# 05_ServoStage_v1.net
KiCad netlist of a schematic drawn in EAGLE
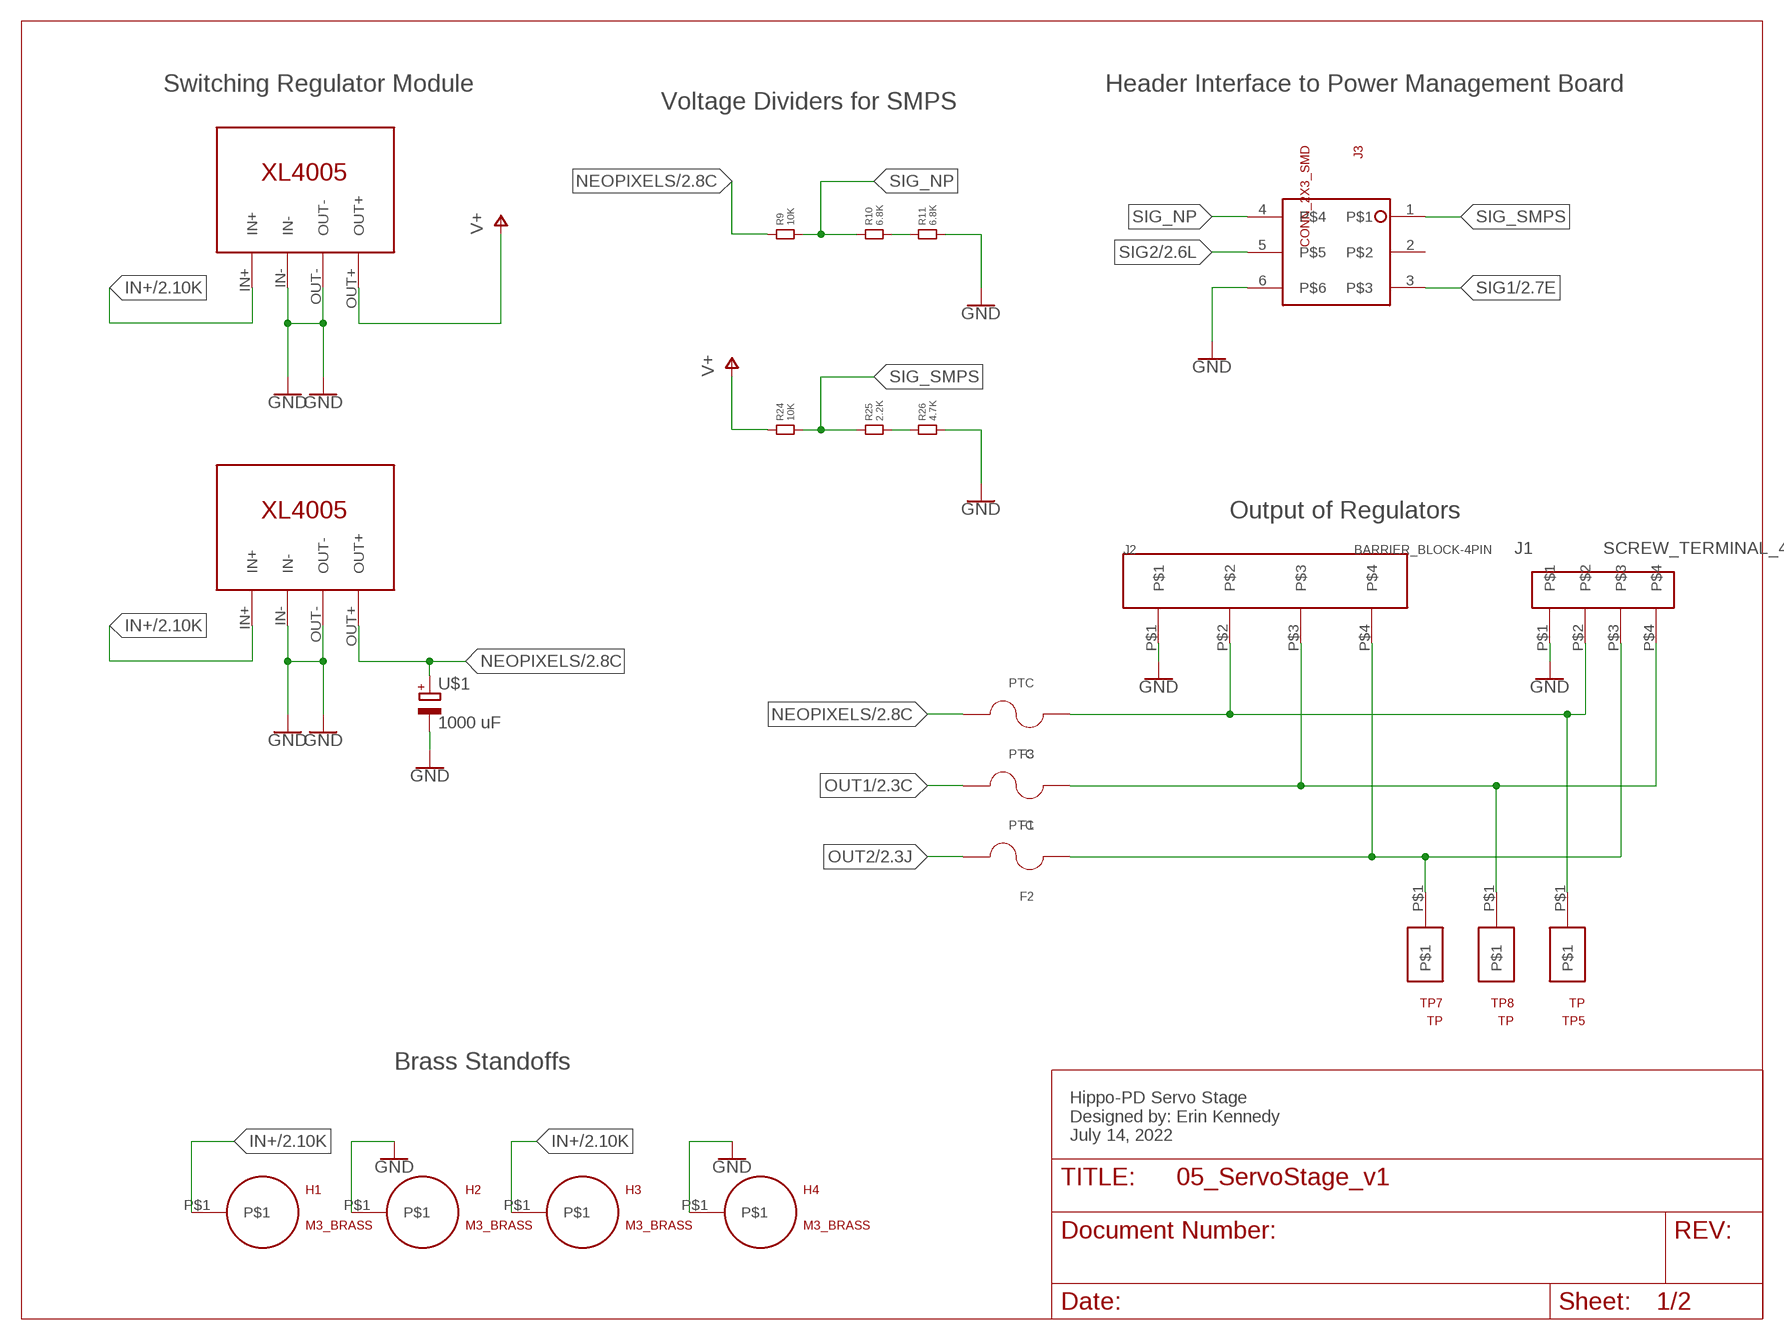
[diagram p0: schematic, sheet 1]
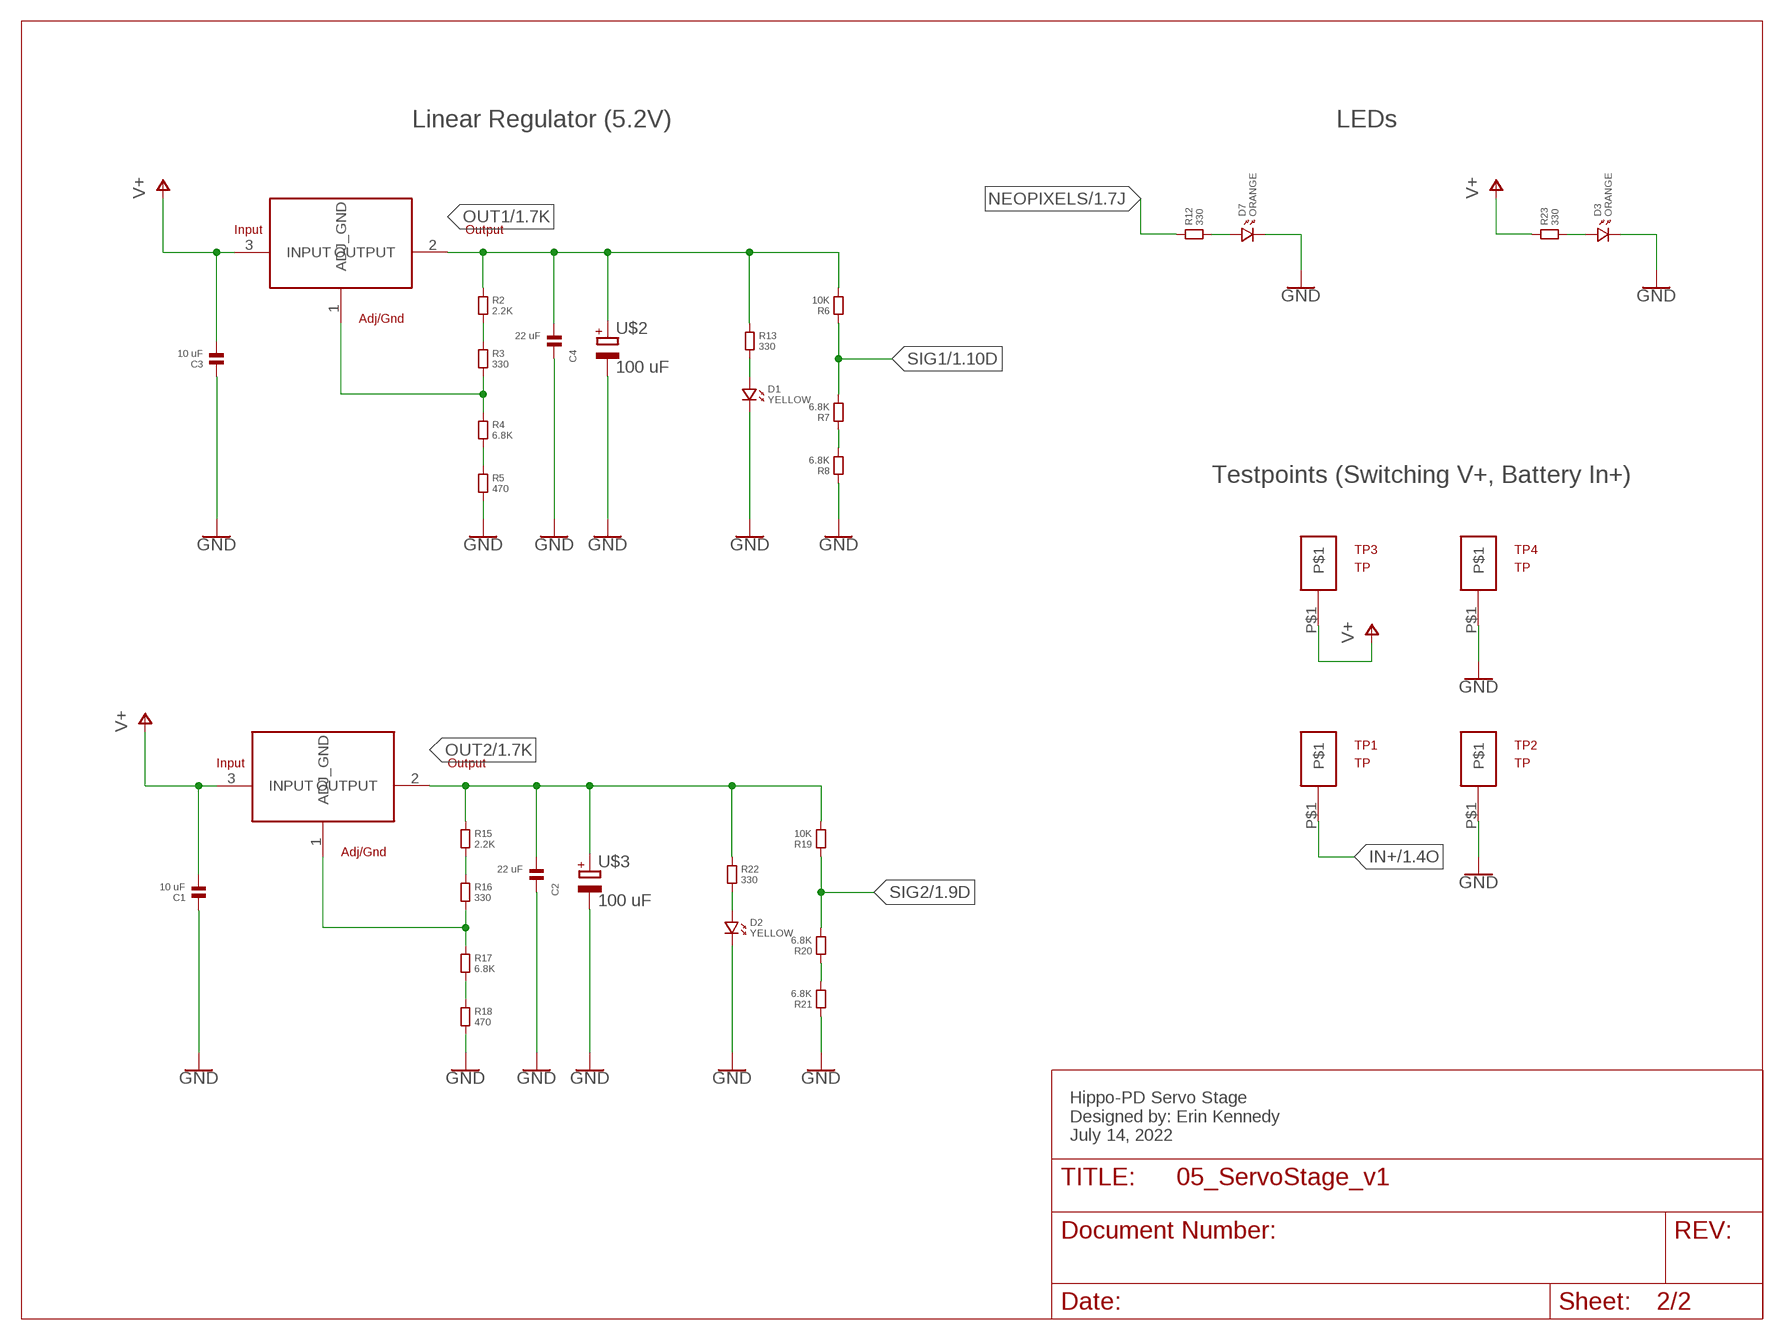
[diagram p1: schematic, sheet 2]

(export (version "E")
  (design (tool "Eeschema 10.0.6"))
  (components
    (comp (ref "C1")
      (value "10 uF")
      (footprint "eagle-import:1206")
      (libsource (lib "eagle-import") (part "CAPACITOR.1206"))
    )
    (comp (ref "C2")
      (value "22 uF")
      (footprint "eagle-import:1206")
      (libsource (lib "eagle-import") (part "CAPACITOR.1206"))
    )
    (comp (ref "C3")
      (value "10 uF")
      (footprint "eagle-import:1206")
      (libsource (lib "eagle-import") (part "CAPACITOR.1206"))
    )
    (comp (ref "C4")
      (value "22 uF")
      (footprint "eagle-import:1206")
      (libsource (lib "eagle-import") (part "CAPACITOR.1206"))
    )
    (comp (ref "D1")
      (value "YELLOW")
      (footprint "eagle-import:1206.LED")
      (libsource (lib "eagle-import") (part "LED.1206"))
    )
    (comp (ref "D2")
      (value "YELLOW")
      (footprint "eagle-import:1206.LED")
      (libsource (lib "eagle-import") (part "LED.1206"))
    )
    (comp (ref "D3")
      (value "ORANGE")
      (footprint "eagle-import:1206.LED")
      (libsource (lib "eagle-import") (part "LED.1206"))
    )
    (comp (ref "D7")
      (value "ORANGE")
      (footprint "eagle-import:1206.LED")
      (libsource (lib "eagle-import") (part "LED.1206"))
    )
    (comp (ref "R1")
      (value "AZ1084C")
      (footprint "eagle-import:AZ1084C")
      (libsource (lib "eagle-import") (part "AZ1084C"))
    )
    (comp (ref "R2")
      (value "2.2K")
      (footprint "eagle-import:1206")
      (libsource (lib "eagle-import") (part "RESISTOR.1206"))
    )
    (comp (ref "R3")
      (value "330")
      (footprint "eagle-import:1206")
      (libsource (lib "eagle-import") (part "RESISTOR.1206"))
    )
    (comp (ref "R4")
      (value "6.8K")
      (footprint "eagle-import:1206")
      (libsource (lib "eagle-import") (part "RESISTOR.1206"))
    )
    (comp (ref "R5")
      (value "470")
      (footprint "eagle-import:1206")
      (libsource (lib "eagle-import") (part "RESISTOR.1206"))
    )
    (comp (ref "R6")
      (value "10K")
      (footprint "eagle-import:1206")
      (libsource (lib "eagle-import") (part "RESISTOR.1206"))
    )
    (comp (ref "R7")
      (value "6.8K")
      (footprint "eagle-import:1206")
      (libsource (lib "eagle-import") (part "RESISTOR.1206"))
    )
    (comp (ref "R8")
      (value "6.8K")
      (footprint "eagle-import:1206")
      (libsource (lib "eagle-import") (part "RESISTOR.1206"))
    )
    (comp (ref "R12")
      (value "330")
      (footprint "eagle-import:1206")
      (libsource (lib "eagle-import") (part "RESISTOR.1206"))
    )
    (comp (ref "R13")
      (value "330")
      (footprint "eagle-import:1206")
      (libsource (lib "eagle-import") (part "RESISTOR.1206"))
    )
    (comp (ref "R14")
      (value "AZ1084C")
      (footprint "eagle-import:AZ1084C")
      (libsource (lib "eagle-import") (part "AZ1084C"))
    )
    (comp (ref "R15")
      (value "2.2K")
      (footprint "eagle-import:1206")
      (libsource (lib "eagle-import") (part "RESISTOR.1206"))
    )
    (comp (ref "R16")
      (value "330")
      (footprint "eagle-import:1206")
      (libsource (lib "eagle-import") (part "RESISTOR.1206"))
    )
    (comp (ref "R17")
      (value "6.8K")
      (footprint "eagle-import:1206")
      (libsource (lib "eagle-import") (part "RESISTOR.1206"))
    )
    (comp (ref "R18")
      (value "470")
      (footprint "eagle-import:1206")
      (libsource (lib "eagle-import") (part "RESISTOR.1206"))
    )
    (comp (ref "R19")
      (value "10K")
      (footprint "eagle-import:1206")
      (libsource (lib "eagle-import") (part "RESISTOR.1206"))
    )
    (comp (ref "R20")
      (value "6.8K")
      (footprint "eagle-import:1206")
      (libsource (lib "eagle-import") (part "RESISTOR.1206"))
    )
    (comp (ref "R21")
      (value "6.8K")
      (footprint "eagle-import:1206")
      (libsource (lib "eagle-import") (part "RESISTOR.1206"))
    )
    (comp (ref "R22")
      (value "330")
      (footprint "eagle-import:1206")
      (libsource (lib "eagle-import") (part "RESISTOR.1206"))
    )
    (comp (ref "R23")
      (value "330")
      (footprint "eagle-import:1206")
      (libsource (lib "eagle-import") (part "RESISTOR.1206"))
    )
    (comp (ref "TP1") (value "TP") (footprint "eagle-import:TP") (libsource (lib "eagle-import") (part "TP")))
    (comp (ref "TP2") (value "TP") (footprint "eagle-import:TP") (libsource (lib "eagle-import") (part "TP")))
    (comp (ref "TP3") (value "TP") (footprint "eagle-import:TP") (libsource (lib "eagle-import") (part "TP")))
    (comp (ref "TP4") (value "TP") (footprint "eagle-import:TP") (libsource (lib "eagle-import") (part "TP")))
    (comp (ref "U$2")
      (value "100 uF")
      (footprint "eagle-import:ELECTROLYTIC_CAP")
      (fields (field (name "MF") "Wurth Electronics") (field (name "MP") "865080545012"))
      (libsource (lib "eagle-import") (part "ELECTROLYTIC_CAP"))
    )
    (comp (ref "U$3")
      (value "100 uF")
      (footprint "eagle-import:ELECTROLYTIC_CAP")
      (fields (field (name "MF") "Wurth Electronics") (field (name "MP") "865080545012"))
      (libsource (lib "eagle-import") (part "ELECTROLYTIC_CAP"))
    )
    (comp (ref "F1")
      (value "PTC")
      (footprint "eagle-import:PTC")
      (fields (field (name "MF") "Bel Fuse") (field (name "MP") "0ZCF0075AF2C"))
      (libsource (lib "eagle-import") (part "PTC"))
    )
    (comp (ref "F2")
      (value "PTC")
      (footprint "eagle-import:PTC")
      (fields (field (name "MF") "Bel Fuse") (field (name "MP") "0ZCF0075AF2C"))
      (libsource (lib "eagle-import") (part "PTC"))
    )
    (comp (ref "F3")
      (value "PTC")
      (footprint "eagle-import:PTC")
      (fields (field (name "MF") "Bel Fuse") (field (name "MP") "0ZCF0075AF2C"))
      (libsource (lib "eagle-import") (part "PTC"))
    )
    (comp (ref "H1")
      (value "M3_BRASS")
      (footprint "eagle-import:M3_BRASS")
      (libsource (lib "eagle-import") (part "M3_BRASS"))
    )
    (comp (ref "H2")
      (value "M3_BRASS")
      (footprint "eagle-import:M3_BRASS")
      (libsource (lib "eagle-import") (part "M3_BRASS"))
    )
    (comp (ref "H3")
      (value "M3_BRASS")
      (footprint "eagle-import:M3_BRASS")
      (libsource (lib "eagle-import") (part "M3_BRASS"))
    )
    (comp (ref "H4")
      (value "M3_BRASS")
      (footprint "eagle-import:M3_BRASS")
      (libsource (lib "eagle-import") (part "M3_BRASS"))
    )
    (comp (ref "J1")
      (value "SCREW_TERMINAL_4")
      (footprint "eagle-import:SCREW_TERM_4")
      (libsource (lib "eagle-import") (part "SCREW_TERMINAL_4"))
    )
    (comp (ref "J2")
      (value "BARRIER_BLOCK-4PIN")
      (footprint "eagle-import:BARRIERBLOCK-4PIN")
      (libsource (lib "eagle-import") (part "BARRIER_BLOCK-4PIN"))
    )
    (comp (ref "J3")
      (value "CONN_2X3_SMD")
      (footprint "eagle-import:2X3_SMD_CONNECTOR")
      (libsource (lib "eagle-import") (part "CONN_2X3_SMD"))
    )
    (comp (ref "R9")
      (value "10K")
      (footprint "eagle-import:1206")
      (libsource (lib "eagle-import") (part "RESISTOR.1206"))
    )
    (comp (ref "R10")
      (value "6.8K")
      (footprint "eagle-import:1206")
      (libsource (lib "eagle-import") (part "RESISTOR.1206"))
    )
    (comp (ref "R11")
      (value "6.8K")
      (footprint "eagle-import:1206")
      (libsource (lib "eagle-import") (part "RESISTOR.1206"))
    )
    (comp (ref "R24")
      (value "10K")
      (footprint "eagle-import:1206")
      (libsource (lib "eagle-import") (part "RESISTOR.1206"))
    )
    (comp (ref "R25")
      (value "2.2K")
      (footprint "eagle-import:1206")
      (libsource (lib "eagle-import") (part "RESISTOR.1206"))
    )
    (comp (ref "R26")
      (value "4.7K")
      (footprint "eagle-import:1206")
      (libsource (lib "eagle-import") (part "RESISTOR.1206"))
    )
    (comp (ref "TP5") (value "TP") (footprint "eagle-import:TP") (libsource (lib "eagle-import") (part "TP")))
    (comp (ref "TP7") (value "TP") (footprint "eagle-import:TP") (libsource (lib "eagle-import") (part "TP")))
    (comp (ref "TP8") (value "TP") (footprint "eagle-import:TP") (libsource (lib "eagle-import") (part "TP")))
    (comp (ref "U$1")
      (value "1000 uF")
      (footprint "eagle-import:ELECTROLYTIC_CAP")
      (fields (field (name "MF") "Wurth Electronics") (field (name "MP") "865080545012"))
      (libsource (lib "eagle-import") (part "ELECTROLYTIC_CAP"))
    )
    (comp (ref "U1")
      (value "XL4005-DEV")
      (footprint "eagle-import:XL4005-DEV")
      (libsource (lib "eagle-import") (part "XL4005-DEV"))
    )
    (comp (ref "U2")
      (value "XL4005-DEV")
      (footprint "eagle-import:XL4005-DEV")
      (libsource (lib "eagle-import") (part "XL4005-DEV"))
    )
  )
  (nets
    (net (code "1") (name "GND") (class "Default")
      (node (ref "C1") (pin "1") (pinfunction "1_1") (pintype "bidirectional"))
      (node (ref "C2") (pin "1") (pinfunction "1_1") (pintype "bidirectional"))
      (node (ref "C3") (pin "1") (pinfunction "1_1") (pintype "bidirectional"))
      (node (ref "C4") (pin "1") (pinfunction "1_1") (pintype "bidirectional"))
      (node (ref "D1") (pin "P$2") (pinfunction "2_P$2") (pintype "bidirectional"))
      (node (ref "D2") (pin "P$2") (pinfunction "2_P$2") (pintype "bidirectional"))
      (node (ref "D3") (pin "P$2") (pinfunction "2_P$2") (pintype "bidirectional"))
      (node (ref "D7") (pin "P$2") (pinfunction "2_P$2") (pintype "bidirectional"))
      (node (ref "H2") (pin "P$1") (pinfunction "P$1_P$1") (pintype "bidirectional"))
      (node (ref "H4") (pin "P$1") (pinfunction "P$1_P$1") (pintype "bidirectional"))
      (node (ref "J1") (pin "P$1") (pinfunction "P$1_P$1") (pintype "bidirectional"))
      (node (ref "J2") (pin "P$1") (pinfunction "P$1_P$1") (pintype "bidirectional"))
      (node (ref "J3") (pin "6") (pinfunction "P$6_6") (pintype "bidirectional"))
      (node (ref "R11") (pin "2") (pinfunction "2_2") (pintype "bidirectional"))
      (node (ref "R18") (pin "2") (pinfunction "2_2") (pintype "bidirectional"))
      (node (ref "R21") (pin "1") (pinfunction "1_1") (pintype "bidirectional"))
      (node (ref "R26") (pin "2") (pinfunction "2_2") (pintype "bidirectional"))
      (node (ref "R5") (pin "2") (pinfunction "2_2") (pintype "bidirectional"))
      (node (ref "R8") (pin "1") (pinfunction "1_1") (pintype "bidirectional"))
      (node (ref "TP2") (pin "P$1") (pinfunction "P$1_P$1") (pintype "bidirectional"))
      (node (ref "TP4") (pin "P$1") (pinfunction "P$1_P$1") (pintype "bidirectional"))
      (node (ref "U$1") (pin "-") (pinfunction "-_-") (pintype "passive"))
      (node (ref "U$2") (pin "-") (pinfunction "-_-") (pintype "passive"))
      (node (ref "U$3") (pin "-") (pinfunction "-_-") (pintype "passive"))
      (node (ref "U1") (pin "IN-") (pinfunction "IN-_IN-") (pintype "bidirectional"))
      (node (ref "U1") (pin "OUT-") (pinfunction "OUT-_OUT-") (pintype "bidirectional"))
      (node (ref "U2") (pin "IN-") (pinfunction "IN-_IN-") (pintype "bidirectional"))
      (node (ref "U2") (pin "OUT-") (pinfunction "OUT-_OUT-") (pintype "bidirectional"))
    )
    (net (code "2") (name "IN+") (class "Default")
      (node (ref "H1") (pin "P$1") (pinfunction "P$1_P$1") (pintype "bidirectional"))
      (node (ref "H3") (pin "P$1") (pinfunction "P$1_P$1") (pintype "bidirectional"))
      (node (ref "TP1") (pin "P$1") (pinfunction "P$1_P$1") (pintype "bidirectional"))
      (node (ref "U1") (pin "IN+") (pinfunction "IN+_IN+") (pintype "bidirectional"))
      (node (ref "U2") (pin "IN+") (pinfunction "IN+_IN+") (pintype "bidirectional"))
    )
    (net (code "3") (name "NEOPIXELS") (class "Default")
      (node (ref "F3") (pin "2") (pinfunction "2_2") (pintype "passive"))
      (node (ref "R12") (pin "1") (pinfunction "1_1") (pintype "bidirectional"))
      (node (ref "R9") (pin "1") (pinfunction "1_1") (pintype "bidirectional"))
      (node (ref "U$1") (pin "+") (pinfunction "+_+") (pintype "passive"))
      (node (ref "U2") (pin "OUT+") (pinfunction "OUT+_OUT+") (pintype "bidirectional"))
    )
    (net (code "4") (name "Net-(D1-1)") (class "Default")
      (node (ref "D1") (pin "P$1") (pinfunction "1_P$1") (pintype "bidirectional"))
      (node (ref "R13") (pin "2") (pinfunction "2_2") (pintype "bidirectional"))
    )
    (net (code "5") (name "Net-(D2-1)") (class "Default")
      (node (ref "D2") (pin "P$1") (pinfunction "1_P$1") (pintype "bidirectional"))
      (node (ref "R22") (pin "2") (pinfunction "2_2") (pintype "bidirectional"))
    )
    (net (code "6") (name "Net-(D3-1)") (class "Default")
      (node (ref "D3") (pin "P$1") (pinfunction "1_P$1") (pintype "bidirectional"))
      (node (ref "R23") (pin "2") (pinfunction "2_2") (pintype "bidirectional"))
    )
    (net (code "7") (name "Net-(D7-1)") (class "Default")
      (node (ref "D7") (pin "P$1") (pinfunction "1_P$1") (pintype "bidirectional"))
      (node (ref "R12") (pin "2") (pinfunction "2_2") (pintype "bidirectional"))
    )
    (net (code "8") (name "Net-(F1-Pad1)") (class "Default")
      (node (ref "F1") (pin "1") (pinfunction "1_1") (pintype "passive"))
      (node (ref "J1") (pin "P$4") (pinfunction "P$4_P$4") (pintype "bidirectional"))
      (node (ref "J2") (pin "P$3") (pinfunction "P$3_P$3") (pintype "bidirectional"))
      (node (ref "TP8") (pin "P$1") (pinfunction "P$1_P$1") (pintype "bidirectional"))
    )
    (net (code "9") (name "Net-(F2-Pad1)") (class "Default")
      (node (ref "F2") (pin "1") (pinfunction "1_1") (pintype "passive"))
      (node (ref "J1") (pin "P$3") (pinfunction "P$3_P$3") (pintype "bidirectional"))
      (node (ref "J2") (pin "P$4") (pinfunction "P$4_P$4") (pintype "bidirectional"))
      (node (ref "TP7") (pin "P$1") (pinfunction "P$1_P$1") (pintype "bidirectional"))
    )
    (net (code "10") (name "Net-(F3-Pad1)") (class "Default")
      (node (ref "F3") (pin "1") (pinfunction "1_1") (pintype "passive"))
      (node (ref "J1") (pin "P$2") (pinfunction "P$2_P$2") (pintype "bidirectional"))
      (node (ref "J2") (pin "P$2") (pinfunction "P$2_P$2") (pintype "bidirectional"))
      (node (ref "TP5") (pin "P$1") (pinfunction "P$1_P$1") (pintype "bidirectional"))
    )
    (net (code "11") (name "Net-(R1-ADJ_GND)") (class "Default")
      (node (ref "R1") (pin "1") (pinfunction "ADJ_GND_1") (pintype "bidirectional"))
      (node (ref "R3") (pin "2") (pinfunction "2_2") (pintype "bidirectional"))
      (node (ref "R4") (pin "1") (pinfunction "1_1") (pintype "bidirectional"))
    )
    (net (code "12") (name "Net-(R2-Pad2)") (class "Default")
      (node (ref "R2") (pin "2") (pinfunction "2_2") (pintype "bidirectional"))
      (node (ref "R3") (pin "1") (pinfunction "1_1") (pintype "bidirectional"))
    )
    (net (code "13") (name "Net-(R4-Pad2)") (class "Default")
      (node (ref "R4") (pin "2") (pinfunction "2_2") (pintype "bidirectional"))
      (node (ref "R5") (pin "1") (pinfunction "1_1") (pintype "bidirectional"))
    )
    (net (code "14") (name "Net-(R7-Pad1)") (class "Default")
      (node (ref "R7") (pin "1") (pinfunction "1_1") (pintype "bidirectional"))
      (node (ref "R8") (pin "2") (pinfunction "2_2") (pintype "bidirectional"))
    )
    (net (code "15") (name "Net-(R10-Pad2)") (class "Default")
      (node (ref "R10") (pin "2") (pinfunction "2_2") (pintype "bidirectional"))
      (node (ref "R11") (pin "1") (pinfunction "1_1") (pintype "bidirectional"))
    )
    (net (code "16") (name "Net-(R14-ADJ_GND)") (class "Default")
      (node (ref "R14") (pin "1") (pinfunction "ADJ_GND_1") (pintype "bidirectional"))
      (node (ref "R16") (pin "2") (pinfunction "2_2") (pintype "bidirectional"))
      (node (ref "R17") (pin "1") (pinfunction "1_1") (pintype "bidirectional"))
    )
    (net (code "17") (name "Net-(R15-Pad2)") (class "Default")
      (node (ref "R15") (pin "2") (pinfunction "2_2") (pintype "bidirectional"))
      (node (ref "R16") (pin "1") (pinfunction "1_1") (pintype "bidirectional"))
    )
    (net (code "18") (name "Net-(R17-Pad2)") (class "Default")
      (node (ref "R17") (pin "2") (pinfunction "2_2") (pintype "bidirectional"))
      (node (ref "R18") (pin "1") (pinfunction "1_1") (pintype "bidirectional"))
    )
    (net (code "19") (name "Net-(R20-Pad1)") (class "Default")
      (node (ref "R20") (pin "1") (pinfunction "1_1") (pintype "bidirectional"))
      (node (ref "R21") (pin "2") (pinfunction "2_2") (pintype "bidirectional"))
    )
    (net (code "20") (name "Net-(R25-Pad2)") (class "Default")
      (node (ref "R25") (pin "2") (pinfunction "2_2") (pintype "bidirectional"))
      (node (ref "R26") (pin "1") (pinfunction "1_1") (pintype "bidirectional"))
    )
    (net (code "21") (name "OUT1") (class "Default")
      (node (ref "C4") (pin "2") (pinfunction "2_2") (pintype "bidirectional"))
      (node (ref "F1") (pin "2") (pinfunction "2_2") (pintype "passive"))
      (node (ref "R1") (pin "2") (pinfunction "OUTPUT_2") (pintype "bidirectional"))
      (node (ref "R13") (pin "1") (pinfunction "1_1") (pintype "bidirectional"))
      (node (ref "R2") (pin "1") (pinfunction "1_1") (pintype "bidirectional"))
      (node (ref "R6") (pin "2") (pinfunction "2_2") (pintype "bidirectional"))
      (node (ref "U$2") (pin "+") (pinfunction "+_+") (pintype "passive"))
    )
    (net (code "22") (name "OUT2") (class "Default")
      (node (ref "C2") (pin "2") (pinfunction "2_2") (pintype "bidirectional"))
      (node (ref "F2") (pin "2") (pinfunction "2_2") (pintype "passive"))
      (node (ref "R14") (pin "2") (pinfunction "OUTPUT_2") (pintype "bidirectional"))
      (node (ref "R15") (pin "1") (pinfunction "1_1") (pintype "bidirectional"))
      (node (ref "R19") (pin "2") (pinfunction "2_2") (pintype "bidirectional"))
      (node (ref "R22") (pin "1") (pinfunction "1_1") (pintype "bidirectional"))
      (node (ref "U$3") (pin "+") (pinfunction "+_+") (pintype "passive"))
    )
    (net (code "23") (name "SIG1") (class "Default")
      (node (ref "J3") (pin "3") (pinfunction "P$3_3") (pintype "bidirectional"))
      (node (ref "R6") (pin "1") (pinfunction "1_1") (pintype "bidirectional"))
      (node (ref "R7") (pin "2") (pinfunction "2_2") (pintype "bidirectional"))
    )
    (net (code "24") (name "SIG2") (class "Default")
      (node (ref "J3") (pin "5") (pinfunction "P$5_5") (pintype "bidirectional"))
      (node (ref "R19") (pin "1") (pinfunction "1_1") (pintype "bidirectional"))
      (node (ref "R20") (pin "2") (pinfunction "2_2") (pintype "bidirectional"))
    )
    (net (code "25") (name "SIG_NP") (class "Default")
      (node (ref "J3") (pin "4") (pinfunction "P$4_4") (pintype "bidirectional"))
      (node (ref "R10") (pin "1") (pinfunction "1_1") (pintype "bidirectional"))
      (node (ref "R9") (pin "2") (pinfunction "2_2") (pintype "bidirectional"))
    )
    (net (code "26") (name "SIG_SMPS") (class "Default")
      (node (ref "J3") (pin "1") (pinfunction "P$1_1") (pintype "bidirectional"))
      (node (ref "R24") (pin "2") (pinfunction "2_2") (pintype "bidirectional"))
      (node (ref "R25") (pin "1") (pinfunction "1_1") (pintype "bidirectional"))
    )
    (net (code "27") (name "V+") (class "Default")
      (node (ref "C1") (pin "2") (pinfunction "2_2") (pintype "bidirectional"))
      (node (ref "C3") (pin "2") (pinfunction "2_2") (pintype "bidirectional"))
      (node (ref "R1") (pin "3") (pinfunction "INPUT_3") (pintype "bidirectional"))
      (node (ref "R14") (pin "3") (pinfunction "INPUT_3") (pintype "bidirectional"))
      (node (ref "R23") (pin "1") (pinfunction "1_1") (pintype "bidirectional"))
      (node (ref "R24") (pin "1") (pinfunction "1_1") (pintype "bidirectional"))
      (node (ref "TP3") (pin "P$1") (pinfunction "P$1_P$1") (pintype "bidirectional"))
      (node (ref "U1") (pin "OUT+") (pinfunction "OUT+_OUT+") (pintype "bidirectional"))
    )
    (net (code "28") (name "unconnected-(J3-P$2-Pad2)") (class "Default")
      (node (ref "J3") (pin "2") (pinfunction "P$2_2") (pintype "bidirectional"))
    )
  )
)
